# Amp.net
KiCad netlist of a schematic drawn in Altium Designer
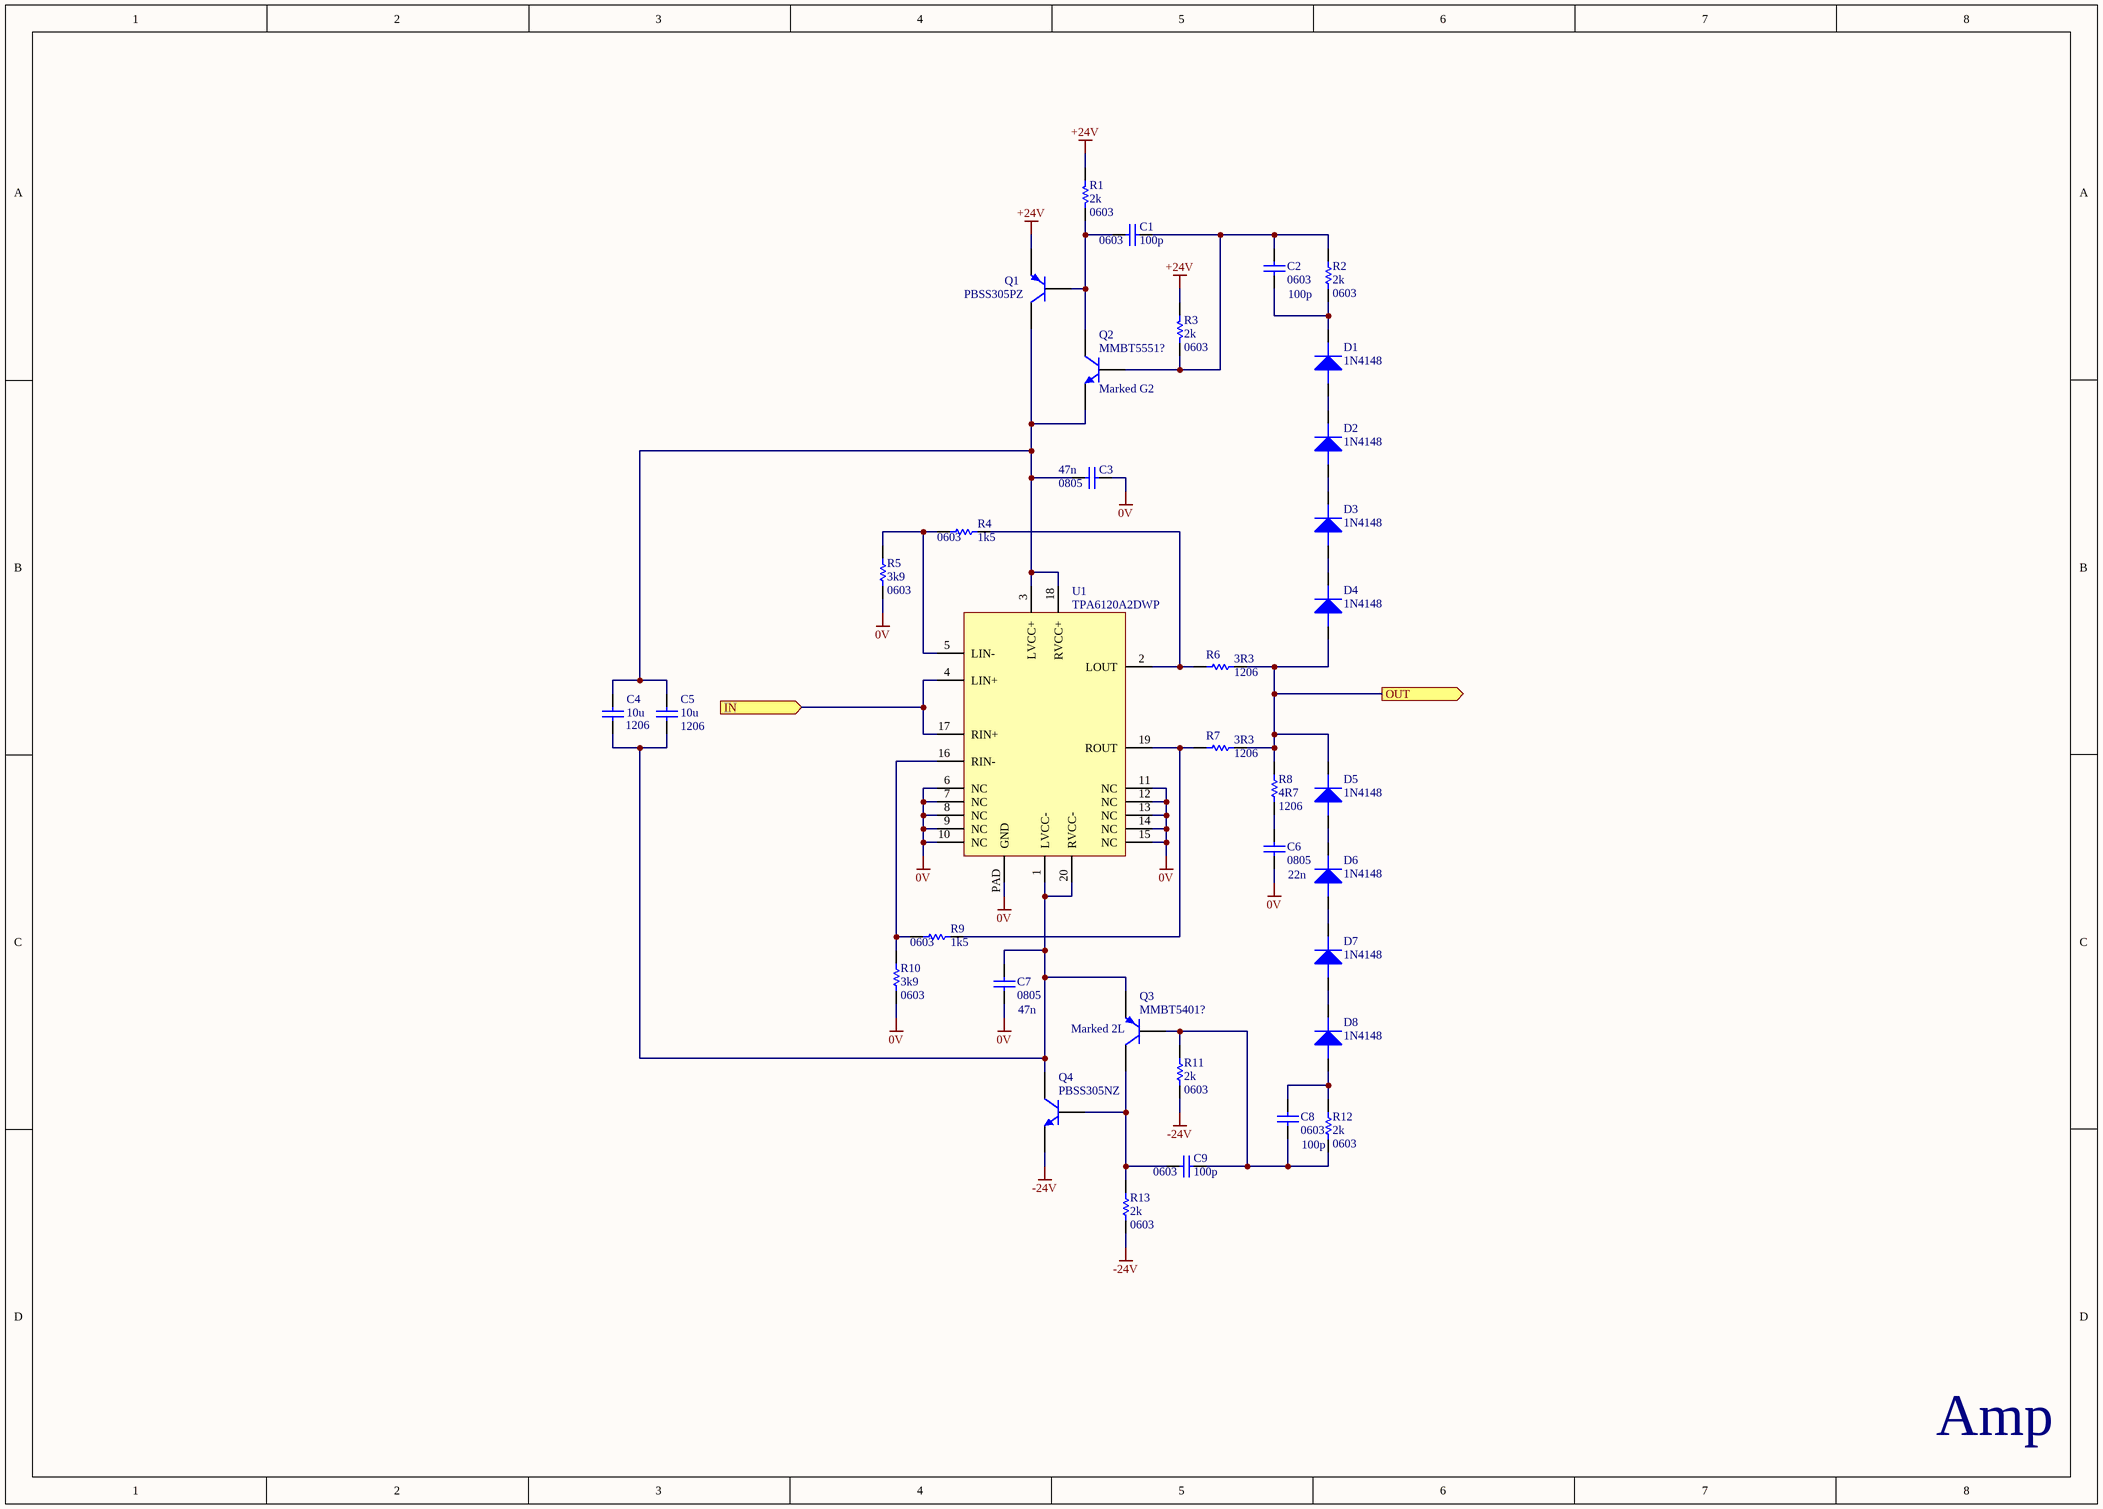
[diagram p0: Amp.SchDoc]

(export (version "E")
  (design (tool "Eeschema 10.0.6"))
  (components
    (comp (ref "C1")
      (value "100p")
      (footprint "CAPC1608X09N")
      (description "Generic MLCC 0603 Non Polarized Capacitor")
      (fields
        (field (name "MANUFACTURER") "Generic")
        (field (name "PACKAGE") "0603")
        (field (name "Comment") "C_MLCC_0603")
      )
      (libsource (lib "Topping_L50") (part "C_MLCC_0603"))
    )
    (comp (ref "C2")
      (value "100p")
      (footprint "CAPC1608X09N")
      (description "Generic MLCC 0603 Non Polarized Capacitor")
      (fields
        (field (name "MANUFACTURER") "Generic")
        (field (name "PACKAGE") "0603")
        (field (name "Comment") "C_MLCC_0603")
      )
      (libsource (lib "Topping_L50") (part "C_MLCC_0603"))
    )
    (comp (ref "C3")
      (value "47n")
      (footprint "CAPC2012X14N")
      (description "Generic MLCC 0805 Non Polarized Capacitor")
      (fields
        (field (name "MANUFACTURER") "Generic")
        (field (name "PACKAGE") "0805")
        (field (name "Comment") "C_MLCC_0805")
      )
      (libsource (lib "Topping_L50") (part "C_MLCC_0805"))
    )
    (comp (ref "C4")
      (value "10u")
      (footprint "C_NP_1206")
      (description "Generic MLCC Non Polarized Capacitor 1206")
      (fields
        (field (name "MANUFACTURER") "Generic")
        (field (name "PACKAGE") "1206")
        (field (name "Comment") "C_MLCC_1206")
      )
      (libsource (lib "Topping_L50") (part "C_MLCC_1206"))
    )
    (comp (ref "C5")
      (value "10u")
      (footprint "C_NP_1206")
      (description "Generic MLCC Non Polarized Capacitor 1206")
      (fields
        (field (name "MANUFACTURER") "Generic")
        (field (name "PACKAGE") "1206")
        (field (name "Comment") "C_MLCC_1206")
      )
      (libsource (lib "Topping_L50") (part "C_MLCC_1206"))
    )
    (comp (ref "C6")
      (value "22n")
      (footprint "CAPC2012X14N")
      (description "Generic MLCC 0805 Non Polarized Capacitor")
      (fields
        (field (name "MANUFACTURER") "Generic")
        (field (name "PACKAGE") "0805")
        (field (name "Comment") "C_MLCC_0805")
      )
      (libsource (lib "Topping_L50") (part "C_MLCC_0805"))
    )
    (comp (ref "C7")
      (value "47n")
      (footprint "CAPC2012X14N")
      (description "Generic MLCC 0805 Non Polarized Capacitor")
      (fields
        (field (name "MANUFACTURER") "Generic")
        (field (name "PACKAGE") "0805")
        (field (name "Comment") "C_MLCC_0805")
      )
      (libsource (lib "Topping_L50") (part "C_MLCC_0805"))
    )
    (comp (ref "C8")
      (value "100p")
      (footprint "CAPC1608X09N")
      (description "Generic MLCC 0603 Non Polarized Capacitor")
      (fields
        (field (name "MANUFACTURER") "Generic")
        (field (name "PACKAGE") "0603")
        (field (name "Comment") "C_MLCC_0603")
      )
      (libsource (lib "Topping_L50") (part "C_MLCC_0603"))
    )
    (comp (ref "C9")
      (value "100p")
      (footprint "CAPC1608X09N")
      (description "Generic MLCC 0603 Non Polarized Capacitor")
      (fields
        (field (name "MANUFACTURER") "Generic")
        (field (name "PACKAGE") "0603")
        (field (name "Comment") "C_MLCC_0603")
      )
      (libsource (lib "Topping_L50") (part "C_MLCC_0603"))
    )
    (comp (ref "D1")
      (value "1N4148")
      (description "Generic small signal diode")
      (fields (field (name "MANUFACTURER") "Generic") (field (name "MANUFACTURER PART NUMBER") "BAT48ZFILM"))
      (libsource (lib "Topping_L50") (part "1N4148"))
    )
    (comp (ref "D2")
      (value "1N4148")
      (description "Generic small signal diode")
      (fields (field (name "MANUFACTURER") "Generic") (field (name "MANUFACTURER PART NUMBER") "BAT48ZFILM"))
      (libsource (lib "Topping_L50") (part "1N4148"))
    )
    (comp (ref "D3")
      (value "1N4148")
      (description "Generic small signal diode")
      (fields (field (name "MANUFACTURER") "Generic") (field (name "MANUFACTURER PART NUMBER") "BAT48ZFILM"))
      (libsource (lib "Topping_L50") (part "1N4148"))
    )
    (comp (ref "D4")
      (value "1N4148")
      (description "Generic small signal diode")
      (fields (field (name "MANUFACTURER") "Generic") (field (name "MANUFACTURER PART NUMBER") "BAT48ZFILM"))
      (libsource (lib "Topping_L50") (part "1N4148"))
    )
    (comp (ref "D5")
      (value "1N4148")
      (description "Generic small signal diode")
      (fields (field (name "MANUFACTURER") "Generic") (field (name "MANUFACTURER PART NUMBER") "BAT48ZFILM"))
      (libsource (lib "Topping_L50") (part "1N4148"))
    )
    (comp (ref "D6")
      (value "1N4148")
      (description "Generic small signal diode")
      (fields (field (name "MANUFACTURER") "Generic") (field (name "MANUFACTURER PART NUMBER") "BAT48ZFILM"))
      (libsource (lib "Topping_L50") (part "1N4148"))
    )
    (comp (ref "D7")
      (value "1N4148")
      (description "Generic small signal diode")
      (fields (field (name "MANUFACTURER") "Generic") (field (name "MANUFACTURER PART NUMBER") "BAT48ZFILM"))
      (libsource (lib "Topping_L50") (part "1N4148"))
    )
    (comp (ref "D8")
      (value "1N4148")
      (description "Generic small signal diode")
      (fields (field (name "MANUFACTURER") "Generic") (field (name "MANUFACTURER PART NUMBER") "BAT48ZFILM"))
      (libsource (lib "Topping_L50") (part "1N4148"))
    )
    (comp (ref "Q1")
      (value "PBSS305PZ")
      (footprint "SOT230P700X165-4N")
      (description "80 V, 5.1 A PNP low VCEsat (BISS) transistor")
      (fields (field (name "MANUFACTURER") "NXP") (field (name "MANUFACTURER PART NUMBER") "DZT2222A-13"))
      (libsource (lib "Topping_L50") (part "PBSS305PZ"))
    )
    (comp (ref "Q2")
      (value "MMBT5551?")
      (footprint "SOT95P230X110-3N")
      (description "NPN General-Purpose\r\nAmplifier")
      (fields (field (name "MANUFACTURER") "On Semi") (field (name "MANUFACTURER PART NUMBER") "MMBT3904VL"))
      (libsource (lib "Topping_L50") (part "MMBT5551"))
    )
    (comp (ref "Q3")
      (value "MMBT5401?")
      (footprint "SOT95P230X110-3N")
      (description "PNP Epitaxial Silicon Transistor")
      (fields (field (name "MANUFACTURER") "On Semi") (field (name "MANUFACTURER PART NUMBER") "MMBT3904VL"))
      (libsource (lib "Topping_L50") (part "MMBT5401"))
    )
    (comp (ref "Q4")
      (value "PBSS305NZ")
      (footprint "SOT230P700X165-4N")
      (description "80 V, 5.1 A NPN low VCEsat (BISS) transistor")
      (fields (field (name "MANUFACTURER") "NXP") (field (name "MANUFACTURER PART NUMBER") "DZT2222A-13"))
      (libsource (lib "Topping_L50") (part "PBSS305NZ"))
    )
    (comp (ref "R1")
      (value "2k")
      (footprint "RESC1608X06N")
      (description "Generic 0603 Single Resistor")
      (fields
        (field (name "MANUFACTURER") "Generic")
        (field (name "PACKAGE") "0603")
        (field (name "Comment") "R")
      )
      (libsource (lib "Topping_L50") (part "R_0603"))
    )
    (comp (ref "R2")
      (value "2k")
      (footprint "RESC1608X06N")
      (description "Generic 0603 Single Resistor")
      (fields
        (field (name "MANUFACTURER") "Generic")
        (field (name "PACKAGE") "0603")
        (field (name "Comment") "R")
      )
      (libsource (lib "Topping_L50") (part "R_0603"))
    )
    (comp (ref "R3")
      (value "2k")
      (footprint "RESC1608X06N")
      (description "Generic 0603 Single Resistor")
      (fields
        (field (name "MANUFACTURER") "Generic")
        (field (name "PACKAGE") "0603")
        (field (name "Comment") "R")
      )
      (libsource (lib "Topping_L50") (part "R_0603"))
    )
    (comp (ref "R4")
      (value "1k5")
      (footprint "RESC1608X06N")
      (description "Generic 0603 Single Resistor")
      (fields
        (field (name "MANUFACTURER") "Generic")
        (field (name "PACKAGE") "0603")
        (field (name "Comment") "R")
      )
      (libsource (lib "Topping_L50") (part "R_0603"))
    )
    (comp (ref "R5")
      (value "3k9")
      (footprint "RESC1608X06N")
      (description "Generic 0603 Single Resistor")
      (fields
        (field (name "MANUFACTURER") "Generic")
        (field (name "PACKAGE") "0603")
        (field (name "Comment") "R")
      )
      (libsource (lib "Topping_L50") (part "R_0603"))
    )
    (comp (ref "R6")
      (value "3R3")
      (footprint "RESC3116X06N")
      (description "Generic 1206 Single Resistor")
      (fields
        (field (name "MANUFACTURER") "Generic")
        (field (name "PACKAGE") "1206")
        (field (name "Comment") "R")
      )
      (libsource (lib "Topping_L50") (part "R_1206"))
    )
    (comp (ref "R7")
      (value "3R3")
      (footprint "RESC3116X06N")
      (description "Generic 1206 Single Resistor")
      (fields
        (field (name "MANUFACTURER") "Generic")
        (field (name "PACKAGE") "1206")
        (field (name "Comment") "R")
      )
      (libsource (lib "Topping_L50") (part "R_1206"))
    )
    (comp (ref "R8")
      (value "4R7")
      (footprint "RESC3116X06N")
      (description "Generic 1206 Single Resistor")
      (fields
        (field (name "MANUFACTURER") "Generic")
        (field (name "PACKAGE") "1206")
        (field (name "Comment") "R")
      )
      (libsource (lib "Topping_L50") (part "R_1206"))
    )
    (comp (ref "R9")
      (value "1k5")
      (footprint "RESC1608X06N")
      (description "Generic 0603 Single Resistor")
      (fields
        (field (name "MANUFACTURER") "Generic")
        (field (name "PACKAGE") "0603")
        (field (name "Comment") "R")
      )
      (libsource (lib "Topping_L50") (part "R_0603"))
    )
    (comp (ref "R10")
      (value "3k9")
      (footprint "RESC1608X06N")
      (description "Generic 0603 Single Resistor")
      (fields
        (field (name "MANUFACTURER") "Generic")
        (field (name "PACKAGE") "0603")
        (field (name "Comment") "R")
      )
      (libsource (lib "Topping_L50") (part "R_0603"))
    )
    (comp (ref "R11")
      (value "2k")
      (footprint "RESC1608X06N")
      (description "Generic 0603 Single Resistor")
      (fields
        (field (name "MANUFACTURER") "Generic")
        (field (name "PACKAGE") "0603")
        (field (name "Comment") "R")
      )
      (libsource (lib "Topping_L50") (part "R_0603"))
    )
    (comp (ref "R12")
      (value "2k")
      (footprint "RESC1608X06N")
      (description "Generic 0603 Single Resistor")
      (fields
        (field (name "MANUFACTURER") "Generic")
        (field (name "PACKAGE") "0603")
        (field (name "Comment") "R")
      )
      (libsource (lib "Topping_L50") (part "R_0603"))
    )
    (comp (ref "R13")
      (value "2k")
      (footprint "RESC1608X06N")
      (description "Generic 0603 Single Resistor")
      (fields
        (field (name "MANUFACTURER") "Generic")
        (field (name "PACKAGE") "0603")
        (field (name "Comment") "R")
      )
      (libsource (lib "Topping_L50") (part "R_0603"))
    )
    (comp (ref "U1")
      (value "TPA6120A2DWP")
      (footprint "SOIC127P1040X265_HS-21N")
      (description "Audio Amplifier, 1.5W, 2 Channel(s), 1 Func, SOIC20")
      (fields
        (field (name "MANUFACTURER") "Texas Instruments")
        (field (name "MANUFACTURER PART NUMBER") "TPA6120A2RGYT")
      )
      (libsource (lib "Topping_L50") (part "TPA6120A2DWP"))
    )
  )
  (nets
    (net (code "1") (name "+24V") (class "Default")
      (node (ref "Q1") (pin "E") (pinfunction "E_E") (pintype "passive"))
      (node (ref "R1") (pin "2") (pinfunction "2_2") (pintype "passive"))
      (node (ref "R3") (pin "2") (pinfunction "2_2") (pintype "passive"))
    )
    (net (code "2") (name "-24V") (class "Default")
      (node (ref "Q4") (pin "E") (pinfunction "E_E") (pintype "passive"))
      (node (ref "R11") (pin "2") (pinfunction "2_2") (pintype "passive"))
      (node (ref "R13") (pin "2") (pinfunction "2_2") (pintype "passive"))
    )
    (net (code "3") (name "/IN") (class "Default")
      (node (ref "U1") (pin "17") (pinfunction "RIN+_17") (pintype "passive"))
      (node (ref "U1") (pin "4") (pinfunction "LIN+_4") (pintype "passive"))
    )
    (net (code "4") (name "/OUT") (class "Default")
      (node (ref "D4") (pin "A") (pinfunction "A_A") (pintype "passive"))
      (node (ref "D5") (pin "K") (pinfunction "K_K") (pintype "passive"))
      (node (ref "R6") (pin "2") (pinfunction "2_2") (pintype "passive"))
      (node (ref "R7") (pin "2") (pinfunction "2_2") (pintype "passive"))
      (node (ref "R8") (pin "2") (pinfunction "2_2") (pintype "passive"))
    )
    (net (code "5") (name "0V") (class "Default")
      (node (ref "C3") (pin "1") (pinfunction "1_1") (pintype "passive"))
      (node (ref "C6") (pin "1") (pinfunction "1_1") (pintype "passive"))
      (node (ref "C7") (pin "1") (pinfunction "1_1") (pintype "passive"))
      (node (ref "R10") (pin "2") (pinfunction "2_2") (pintype "passive"))
      (node (ref "R5") (pin "2") (pinfunction "2_2") (pintype "passive"))
      (node (ref "U1") (pin "10") (pinfunction "NC_10") (pintype "passive"))
      (node (ref "U1") (pin "11") (pinfunction "NC_11") (pintype "passive"))
      (node (ref "U1") (pin "12") (pinfunction "NC_12") (pintype "passive"))
      (node (ref "U1") (pin "13") (pinfunction "NC_13") (pintype "passive"))
      (node (ref "U1") (pin "14") (pinfunction "NC_14") (pintype "passive"))
      (node (ref "U1") (pin "15") (pinfunction "NC_15") (pintype "passive"))
      (node (ref "U1") (pin "6") (pinfunction "NC_6") (pintype "passive"))
      (node (ref "U1") (pin "7") (pinfunction "NC_7") (pintype "passive"))
      (node (ref "U1") (pin "8") (pinfunction "NC_8") (pintype "passive"))
      (node (ref "U1") (pin "9") (pinfunction "NC_9") (pintype "passive"))
      (node (ref "U1") (pin "PAD") (pinfunction "GND_PAD") (pintype "passive"))
    )
    (net (code "6") (name "Net-(C1-Pad1)") (class "Default")
      (node (ref "C1") (pin "1") (pinfunction "1_1") (pintype "passive"))
      (node (ref "Q1") (pin "B") (pinfunction "B_B") (pintype "passive"))
      (node (ref "Q2") (pin "C") (pinfunction "C_C") (pintype "passive"))
      (node (ref "R1") (pin "1") (pinfunction "1_1") (pintype "passive"))
    )
    (net (code "7") (name "Net-(C1-Pad2)") (class "Default")
      (node (ref "C1") (pin "2") (pinfunction "2_2") (pintype "passive"))
      (node (ref "C2") (pin "1") (pinfunction "1_1") (pintype "passive"))
      (node (ref "Q2") (pin "B") (pinfunction "B_B") (pintype "passive"))
      (node (ref "R2") (pin "1") (pinfunction "1_1") (pintype "passive"))
      (node (ref "R3") (pin "1") (pinfunction "1_1") (pintype "passive"))
    )
    (net (code "8") (name "Net-(C2-Pad2)") (class "Default")
      (node (ref "C2") (pin "2") (pinfunction "2_2") (pintype "passive"))
      (node (ref "D1") (pin "K") (pinfunction "K_K") (pintype "passive"))
      (node (ref "R2") (pin "2") (pinfunction "2_2") (pintype "passive"))
    )
    (net (code "9") (name "Net-(C6-Pad2)") (class "Default")
      (node (ref "C6") (pin "2") (pinfunction "2_2") (pintype "passive"))
      (node (ref "R8") (pin "1") (pinfunction "1_1") (pintype "passive"))
    )
    (net (code "10") (name "Net-(C8-Pad1)") (class "Default")
      (node (ref "C8") (pin "1") (pinfunction "1_1") (pintype "passive"))
      (node (ref "D8") (pin "A") (pinfunction "A_A") (pintype "passive"))
      (node (ref "R12") (pin "1") (pinfunction "1_1") (pintype "passive"))
    )
    (net (code "11") (name "Net-(C8-Pad2)") (class "Default")
      (node (ref "C8") (pin "2") (pinfunction "2_2") (pintype "passive"))
      (node (ref "C9") (pin "2") (pinfunction "2_2") (pintype "passive"))
      (node (ref "Q3") (pin "B") (pinfunction "B_B") (pintype "passive"))
      (node (ref "R11") (pin "1") (pinfunction "1_1") (pintype "passive"))
      (node (ref "R12") (pin "2") (pinfunction "2_2") (pintype "passive"))
    )
    (net (code "12") (name "Net-(C9-Pad1)") (class "Default")
      (node (ref "C9") (pin "1") (pinfunction "1_1") (pintype "passive"))
      (node (ref "Q3") (pin "C") (pinfunction "C_C") (pintype "passive"))
      (node (ref "Q4") (pin "B") (pinfunction "B_B") (pintype "passive"))
      (node (ref "R13") (pin "1") (pinfunction "1_1") (pintype "passive"))
    )
    (net (code "13") (name "Net-(D1-PadA)") (class "Default")
      (node (ref "D1") (pin "A") (pinfunction "A_A") (pintype "passive"))
      (node (ref "D2") (pin "K") (pinfunction "K_K") (pintype "passive"))
    )
    (net (code "14") (name "Net-(D2-PadA)") (class "Default")
      (node (ref "D2") (pin "A") (pinfunction "A_A") (pintype "passive"))
      (node (ref "D3") (pin "K") (pinfunction "K_K") (pintype "passive"))
    )
    (net (code "15") (name "Net-(D3-PadA)") (class "Default")
      (node (ref "D3") (pin "A") (pinfunction "A_A") (pintype "passive"))
      (node (ref "D4") (pin "K") (pinfunction "K_K") (pintype "passive"))
    )
    (net (code "16") (name "Net-(D5-PadA)") (class "Default")
      (node (ref "D5") (pin "A") (pinfunction "A_A") (pintype "passive"))
      (node (ref "D6") (pin "K") (pinfunction "K_K") (pintype "passive"))
    )
    (net (code "17") (name "Net-(D6-PadA)") (class "Default")
      (node (ref "D6") (pin "A") (pinfunction "A_A") (pintype "passive"))
      (node (ref "D7") (pin "K") (pinfunction "K_K") (pintype "passive"))
    )
    (net (code "18") (name "Net-(D7-PadA)") (class "Default")
      (node (ref "D7") (pin "A") (pinfunction "A_A") (pintype "passive"))
      (node (ref "D8") (pin "K") (pinfunction "K_K") (pintype "passive"))
    )
    (net (code "19") (name "Net-(U1-LIN-)") (class "Default")
      (node (ref "R4") (pin "2") (pinfunction "2_2") (pintype "passive"))
      (node (ref "R5") (pin "1") (pinfunction "1_1") (pintype "passive"))
      (node (ref "U1") (pin "5") (pinfunction "LIN-_5") (pintype "passive"))
    )
    (net (code "20") (name "Net-(U1-LOUT)") (class "Default")
      (node (ref "R4") (pin "1") (pinfunction "1_1") (pintype "passive"))
      (node (ref "R6") (pin "1") (pinfunction "1_1") (pintype "passive"))
      (node (ref "U1") (pin "2") (pinfunction "LOUT_2") (pintype "passive"))
    )
    (net (code "21") (name "Net-(U1-LVCC+)") (class "Default")
      (node (ref "C3") (pin "2") (pinfunction "2_2") (pintype "passive"))
      (node (ref "C4") (pin "1") (pinfunction "1_1") (pintype "passive"))
      (node (ref "C5") (pin "1") (pinfunction "1_1") (pintype "passive"))
      (node (ref "Q1") (pin "C") (pinfunction "C_C") (pintype "passive"))
      (node (ref "Q2") (pin "E") (pinfunction "E_E") (pintype "passive"))
      (node (ref "U1") (pin "18") (pinfunction "RVCC+_18") (pintype "passive"))
      (node (ref "U1") (pin "3") (pinfunction "LVCC+_3") (pintype "passive"))
    )
    (net (code "22") (name "Net-(U1-LVCC-)") (class "Default")
      (node (ref "C4") (pin "2") (pinfunction "2_2") (pintype "passive"))
      (node (ref "C5") (pin "2") (pinfunction "2_2") (pintype "passive"))
      (node (ref "C7") (pin "2") (pinfunction "2_2") (pintype "passive"))
      (node (ref "Q3") (pin "E") (pinfunction "E_E") (pintype "passive"))
      (node (ref "Q4") (pin "C") (pinfunction "C_C") (pintype "passive"))
      (node (ref "U1") (pin "1") (pinfunction "LVCC-_1") (pintype "passive"))
      (node (ref "U1") (pin "20") (pinfunction "RVCC-_20") (pintype "passive"))
    )
    (net (code "23") (name "Net-(U1-RIN-)") (class "Default")
      (node (ref "R10") (pin "1") (pinfunction "1_1") (pintype "passive"))
      (node (ref "R9") (pin "2") (pinfunction "2_2") (pintype "passive"))
      (node (ref "U1") (pin "16") (pinfunction "RIN-_16") (pintype "passive"))
    )
    (net (code "24") (name "Net-(U1-ROUT)") (class "Default")
      (node (ref "R7") (pin "1") (pinfunction "1_1") (pintype "passive"))
      (node (ref "R9") (pin "1") (pinfunction "1_1") (pintype "passive"))
      (node (ref "U1") (pin "19") (pinfunction "ROUT_19") (pintype "passive"))
    )
  )
)
